# Occulow-Breakout.net
KiCad netlist of a schematic drawn in EAGLE
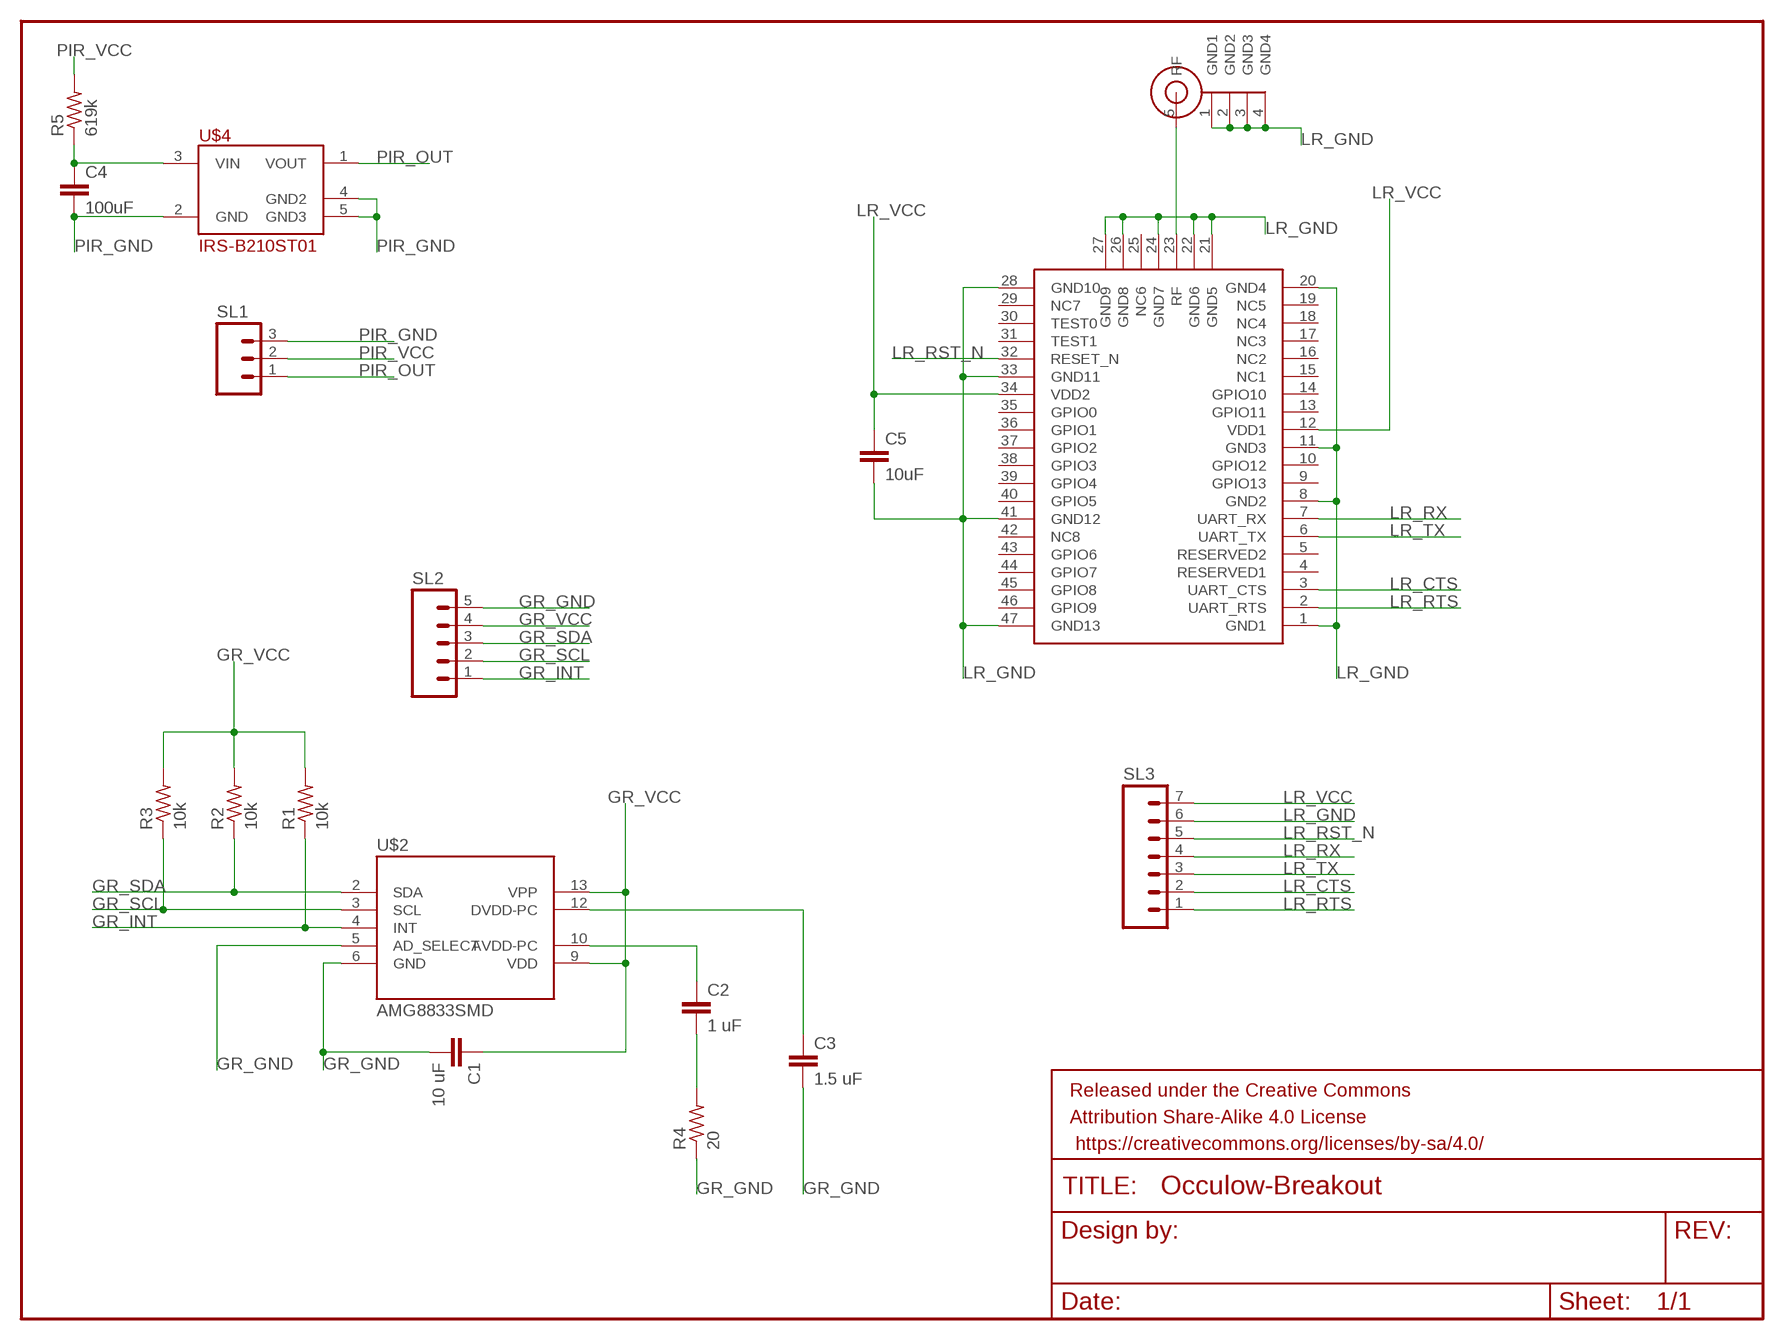
[diagram p0: schematic, sheet 1]

(export (version "E")
  (design (tool "Eeschema 10.0.6"))
  (components
    (comp (ref "C1")
      (value "10 uF")
      (footprint "eagle-import:C1206")
      (libsource (lib "eagle-import") (part "C-EUC1206"))
    )
    (comp (ref "C2")
      (value "1 uF")
      (footprint "eagle-import:C1206")
      (libsource (lib "eagle-import") (part "C-EUC1206"))
    )
    (comp (ref "C3")
      (value "1.5 uF")
      (footprint "eagle-import:C1206")
      (libsource (lib "eagle-import") (part "C-EUC1206"))
    )
    (comp (ref "C4")
      (value "100uF")
      (footprint "eagle-import:C1206")
      (libsource (lib "eagle-import") (part "C-EUC1206"))
    )
    (comp (ref "C5")
      (value "10uF")
      (footprint "eagle-import:C1206")
      (libsource (lib "eagle-import") (part "C-EUC1206"))
    )
    (comp (ref "FRAME1")
      (value "FRAME-LETTER")
      (footprint "eagle-import:CREATIVE_COMMONS")
      (libsource (lib "eagle-import") (part "FRAME-LETTER"))
    )
    (comp (ref "R1")
      (value "10k")
      (footprint "eagle-import:R1206")
      (libsource (lib "eagle-import") (part "R-US_R1206"))
    )
    (comp (ref "R2")
      (value "10k")
      (footprint "eagle-import:R1206")
      (libsource (lib "eagle-import") (part "R-US_R1206"))
    )
    (comp (ref "R3")
      (value "10k")
      (footprint "eagle-import:R1206")
      (libsource (lib "eagle-import") (part "R-US_R1206"))
    )
    (comp (ref "R4")
      (value "20")
      (footprint "eagle-import:R1206")
      (libsource (lib "eagle-import") (part "R-US_R1206"))
    )
    (comp (ref "R5")
      (value "619k")
      (footprint "eagle-import:R1206")
      (libsource (lib "eagle-import") (part "R-US_R1206"))
    )
    (comp (ref "SL1")
      (value "M03")
      (footprint "eagle-import:03P")
      (libsource (lib "eagle-import") (part "M03"))
    )
    (comp (ref "SL2")
      (value "M05")
      (footprint "eagle-import:05P")
      (libsource (lib "eagle-import") (part "M05"))
    )
    (comp (ref "SL3")
      (value "M07")
      (footprint "eagle-import:07P")
      (libsource (lib "eagle-import") (part "M07"))
    )
    (comp (ref "U$1")
      (value "RN2903")
      (footprint "eagle-import:RN2903")
      (libsource (lib "eagle-import") (part "RN2903"))
    )
    (comp (ref "U$2")
      (value "AMG8833SMD")
      (footprint "eagle-import:AMG8833")
      (libsource (lib "eagle-import") (part "AMG8833SMD"))
    )
    (comp (ref "U$3")
      (value "SMA-JACKFEMALE")
      (footprint "eagle-import:SMA-JACK")
      (libsource (lib "eagle-import") (part "SMA-JACKFEMALE"))
    )
    (comp (ref "U$4")
      (value "IRS-B210ST01")
      (footprint "eagle-import:IRS-B210ST01")
      (libsource (lib "eagle-import") (part "IRS-B210ST01"))
    )
  )
  (nets
    (net (code "1") (name "/GR_GND") (class "Default")
      (node (ref "C1") (pin "2") (pinfunction "2_2") (pintype "passive"))
      (node (ref "C3") (pin "2") (pinfunction "2_2") (pintype "passive"))
      (node (ref "R4") (pin "1") (pinfunction "1_1") (pintype "passive"))
      (node (ref "SL2") (pin "5") (pinfunction "5_5") (pintype "passive"))
      (node (ref "U$2") (pin "5") (pinfunction "AD_SELECT_5") (pintype "bidirectional"))
      (node (ref "U$2") (pin "6") (pinfunction "GND_6") (pintype "bidirectional"))
    )
    (net (code "2") (name "/GR_INT") (class "Default")
      (node (ref "R1") (pin "1") (pinfunction "1_1") (pintype "passive"))
      (node (ref "SL2") (pin "1") (pinfunction "1_1") (pintype "passive"))
      (node (ref "U$2") (pin "4") (pinfunction "INT_4") (pintype "bidirectional"))
    )
    (net (code "3") (name "/GR_SCL") (class "Default")
      (node (ref "R3") (pin "1") (pinfunction "1_1") (pintype "passive"))
      (node (ref "SL2") (pin "2") (pinfunction "2_2") (pintype "passive"))
      (node (ref "U$2") (pin "3") (pinfunction "SCL_3") (pintype "bidirectional"))
    )
    (net (code "4") (name "/GR_SDA") (class "Default")
      (node (ref "R2") (pin "1") (pinfunction "1_1") (pintype "passive"))
      (node (ref "SL2") (pin "3") (pinfunction "3_3") (pintype "passive"))
      (node (ref "U$2") (pin "2") (pinfunction "SDA_2") (pintype "bidirectional"))
    )
    (net (code "5") (name "/GR_VCC") (class "Default")
      (node (ref "C1") (pin "1") (pinfunction "1_1") (pintype "passive"))
      (node (ref "R1") (pin "2") (pinfunction "2_2") (pintype "passive"))
      (node (ref "R2") (pin "2") (pinfunction "2_2") (pintype "passive"))
      (node (ref "R3") (pin "2") (pinfunction "2_2") (pintype "passive"))
      (node (ref "SL2") (pin "4") (pinfunction "4_4") (pintype "passive"))
      (node (ref "U$2") (pin "13") (pinfunction "VPP_13") (pintype "bidirectional"))
      (node (ref "U$2") (pin "9") (pinfunction "VDD_9") (pintype "bidirectional"))
    )
    (net (code "6") (name "/LR_CTS") (class "Default")
      (node (ref "SL3") (pin "2") (pinfunction "2_2") (pintype "passive"))
      (node (ref "U$1") (pin "3") (pinfunction "UART_CTS_3") (pintype "bidirectional"))
    )
    (net (code "7") (name "/LR_GND") (class "Default")
      (node (ref "C5") (pin "2") (pinfunction "2_2") (pintype "passive"))
      (node (ref "SL3") (pin "6") (pinfunction "6_6") (pintype "passive"))
      (node (ref "U$1") (pin "1") (pinfunction "GND1_1") (pintype "bidirectional"))
      (node (ref "U$1") (pin "11") (pinfunction "GND3_11") (pintype "bidirectional"))
      (node (ref "U$1") (pin "20") (pinfunction "GND4_20") (pintype "bidirectional"))
      (node (ref "U$1") (pin "21") (pinfunction "GND5_21") (pintype "bidirectional"))
      (node (ref "U$1") (pin "22") (pinfunction "GND6_22") (pintype "bidirectional"))
      (node (ref "U$1") (pin "24") (pinfunction "GND7_24") (pintype "bidirectional"))
      (node (ref "U$1") (pin "26") (pinfunction "GND8_26") (pintype "bidirectional"))
      (node (ref "U$1") (pin "27") (pinfunction "GND9_27") (pintype "bidirectional"))
      (node (ref "U$1") (pin "28") (pinfunction "GND10_28") (pintype "bidirectional"))
      (node (ref "U$1") (pin "33") (pinfunction "GND11_33") (pintype "bidirectional"))
      (node (ref "U$1") (pin "41") (pinfunction "GND12_41") (pintype "bidirectional"))
      (node (ref "U$1") (pin "47") (pinfunction "GND13_47") (pintype "bidirectional"))
      (node (ref "U$1") (pin "8") (pinfunction "GND2_8") (pintype "bidirectional"))
      (node (ref "U$3") (pin "1") (pinfunction "GND1_1") (pintype "bidirectional"))
      (node (ref "U$3") (pin "2") (pinfunction "GND2_2") (pintype "bidirectional"))
      (node (ref "U$3") (pin "3") (pinfunction "GND3_3") (pintype "bidirectional"))
      (node (ref "U$3") (pin "4") (pinfunction "GND4_4") (pintype "bidirectional"))
    )
    (net (code "8") (name "/LR_RST_N") (class "Default")
      (node (ref "SL3") (pin "5") (pinfunction "5_5") (pintype "passive"))
      (node (ref "U$1") (pin "32") (pinfunction "RESET_N_32") (pintype "bidirectional"))
    )
    (net (code "9") (name "/LR_RTS") (class "Default")
      (node (ref "SL3") (pin "1") (pinfunction "1_1") (pintype "passive"))
      (node (ref "U$1") (pin "2") (pinfunction "UART_RTS_2") (pintype "bidirectional"))
    )
    (net (code "10") (name "/LR_RX") (class "Default")
      (node (ref "SL3") (pin "4") (pinfunction "4_4") (pintype "passive"))
      (node (ref "U$1") (pin "7") (pinfunction "UART_RX_7") (pintype "bidirectional"))
    )
    (net (code "11") (name "/LR_TX") (class "Default")
      (node (ref "SL3") (pin "3") (pinfunction "3_3") (pintype "passive"))
      (node (ref "U$1") (pin "6") (pinfunction "UART_TX_6") (pintype "bidirectional"))
    )
    (net (code "12") (name "/LR_VCC") (class "Default")
      (node (ref "C5") (pin "1") (pinfunction "1_1") (pintype "passive"))
      (node (ref "SL3") (pin "7") (pinfunction "7_7") (pintype "passive"))
      (node (ref "U$1") (pin "12") (pinfunction "VDD1_12") (pintype "bidirectional"))
      (node (ref "U$1") (pin "34") (pinfunction "VDD2_34") (pintype "bidirectional"))
    )
    (net (code "13") (name "/PIR_GND") (class "Default")
      (node (ref "C4") (pin "2") (pinfunction "2_2") (pintype "passive"))
      (node (ref "SL1") (pin "3") (pinfunction "3_3") (pintype "passive"))
      (node (ref "U$4") (pin "2") (pinfunction "GND_2") (pintype "bidirectional"))
      (node (ref "U$4") (pin "4") (pinfunction "GND2_4") (pintype "bidirectional"))
      (node (ref "U$4") (pin "5") (pinfunction "GND3_5") (pintype "bidirectional"))
    )
    (net (code "14") (name "/PIR_OUT") (class "Default")
      (node (ref "SL1") (pin "1") (pinfunction "1_1") (pintype "passive"))
      (node (ref "U$4") (pin "1") (pinfunction "VOUT_1") (pintype "bidirectional"))
    )
    (net (code "15") (name "/PIR_VCC") (class "Default")
      (node (ref "R5") (pin "2") (pinfunction "2_2") (pintype "passive"))
      (node (ref "SL1") (pin "2") (pinfunction "2_2") (pintype "passive"))
    )
    (net (code "16") (name "Net-(C2-Pad2)") (class "Default")
      (node (ref "C2") (pin "2") (pinfunction "2_2") (pintype "passive"))
      (node (ref "R4") (pin "2") (pinfunction "2_2") (pintype "passive"))
    )
    (net (code "17") (name "Net-(U$1-RF)") (class "Default")
      (node (ref "U$1") (pin "23") (pinfunction "RF_23") (pintype "bidirectional"))
      (node (ref "U$3") (pin "5") (pinfunction "RF_5") (pintype "bidirectional"))
    )
    (net (code "18") (name "Net-(U$2-AVDD-PC)") (class "Default")
      (node (ref "C2") (pin "1") (pinfunction "1_1") (pintype "passive"))
      (node (ref "U$2") (pin "10") (pinfunction "AVDD-PC_10") (pintype "bidirectional"))
    )
    (net (code "19") (name "Net-(U$2-DVDD-PC)") (class "Default")
      (node (ref "C3") (pin "1") (pinfunction "1_1") (pintype "passive"))
      (node (ref "U$2") (pin "12") (pinfunction "DVDD-PC_12") (pintype "bidirectional"))
    )
    (net (code "20") (name "Net-(U$4-VIN)") (class "Default")
      (node (ref "C4") (pin "1") (pinfunction "1_1") (pintype "passive"))
      (node (ref "R5") (pin "1") (pinfunction "1_1") (pintype "passive"))
      (node (ref "U$4") (pin "3") (pinfunction "VIN_3") (pintype "bidirectional"))
    )
    (net (code "21") (name "unconnected-(U$1-GPIO0-Pad35)") (class "Default")
      (node (ref "U$1") (pin "35") (pinfunction "GPIO0_35") (pintype "bidirectional"))
    )
    (net (code "22") (name "unconnected-(U$1-GPIO1-Pad36)") (class "Default")
      (node (ref "U$1") (pin "36") (pinfunction "GPIO1_36") (pintype "bidirectional"))
    )
    (net (code "23") (name "unconnected-(U$1-GPIO2-Pad37)") (class "Default")
      (node (ref "U$1") (pin "37") (pinfunction "GPIO2_37") (pintype "bidirectional"))
    )
    (net (code "24") (name "unconnected-(U$1-GPIO3-Pad38)") (class "Default")
      (node (ref "U$1") (pin "38") (pinfunction "GPIO3_38") (pintype "bidirectional"))
    )
    (net (code "25") (name "unconnected-(U$1-GPIO4-Pad39)") (class "Default")
      (node (ref "U$1") (pin "39") (pinfunction "GPIO4_39") (pintype "bidirectional"))
    )
    (net (code "26") (name "unconnected-(U$1-GPIO5-Pad40)") (class "Default")
      (node (ref "U$1") (pin "40") (pinfunction "GPIO5_40") (pintype "bidirectional"))
    )
    (net (code "27") (name "unconnected-(U$1-GPIO6-Pad43)") (class "Default")
      (node (ref "U$1") (pin "43") (pinfunction "GPIO6_43") (pintype "bidirectional"))
    )
    (net (code "28") (name "unconnected-(U$1-GPIO7-Pad44)") (class "Default")
      (node (ref "U$1") (pin "44") (pinfunction "GPIO7_44") (pintype "bidirectional"))
    )
    (net (code "29") (name "unconnected-(U$1-GPIO8-Pad45)") (class "Default")
      (node (ref "U$1") (pin "45") (pinfunction "GPIO8_45") (pintype "bidirectional"))
    )
    (net (code "30") (name "unconnected-(U$1-GPIO9-Pad46)") (class "Default")
      (node (ref "U$1") (pin "46") (pinfunction "GPIO9_46") (pintype "bidirectional"))
    )
    (net (code "31") (name "unconnected-(U$1-GPIO10-Pad14)") (class "Default")
      (node (ref "U$1") (pin "14") (pinfunction "GPIO10_14") (pintype "bidirectional"))
    )
    (net (code "32") (name "unconnected-(U$1-GPIO11-Pad13)") (class "Default")
      (node (ref "U$1") (pin "13") (pinfunction "GPIO11_13") (pintype "bidirectional"))
    )
    (net (code "33") (name "unconnected-(U$1-GPIO12-Pad10)") (class "Default")
      (node (ref "U$1") (pin "10") (pinfunction "GPIO12_10") (pintype "bidirectional"))
    )
    (net (code "34") (name "unconnected-(U$1-GPIO13-Pad9)") (class "Default")
      (node (ref "U$1") (pin "9") (pinfunction "GPIO13_9") (pintype "bidirectional"))
    )
    (net (code "35") (name "unconnected-(U$1-NC1-Pad15)") (class "Default")
      (node (ref "U$1") (pin "15") (pinfunction "NC1_15") (pintype "bidirectional"))
    )
    (net (code "36") (name "unconnected-(U$1-NC2-Pad16)") (class "Default")
      (node (ref "U$1") (pin "16") (pinfunction "NC2_16") (pintype "bidirectional"))
    )
    (net (code "37") (name "unconnected-(U$1-NC3-Pad17)") (class "Default")
      (node (ref "U$1") (pin "17") (pinfunction "NC3_17") (pintype "bidirectional"))
    )
    (net (code "38") (name "unconnected-(U$1-NC4-Pad18)") (class "Default")
      (node (ref "U$1") (pin "18") (pinfunction "NC4_18") (pintype "bidirectional"))
    )
    (net (code "39") (name "unconnected-(U$1-NC5-Pad19)") (class "Default")
      (node (ref "U$1") (pin "19") (pinfunction "NC5_19") (pintype "bidirectional"))
    )
    (net (code "40") (name "unconnected-(U$1-NC6-Pad25)") (class "Default")
      (node (ref "U$1") (pin "25") (pinfunction "NC6_25") (pintype "bidirectional"))
    )
    (net (code "41") (name "unconnected-(U$1-NC7-Pad29)") (class "Default")
      (node (ref "U$1") (pin "29") (pinfunction "NC7_29") (pintype "bidirectional"))
    )
    (net (code "42") (name "unconnected-(U$1-NC8-Pad42)") (class "Default")
      (node (ref "U$1") (pin "42") (pinfunction "NC8_42") (pintype "bidirectional"))
    )
    (net (code "43") (name "unconnected-(U$1-RESERVED1-Pad4)") (class "Default")
      (node (ref "U$1") (pin "4") (pinfunction "RESERVED1_4") (pintype "bidirectional"))
    )
    (net (code "44") (name "unconnected-(U$1-RESERVED2-Pad5)") (class "Default")
      (node (ref "U$1") (pin "5") (pinfunction "RESERVED2_5") (pintype "bidirectional"))
    )
    (net (code "45") (name "unconnected-(U$1-TEST0-Pad30)") (class "Default")
      (node (ref "U$1") (pin "30") (pinfunction "TEST0_30") (pintype "bidirectional"))
    )
    (net (code "46") (name "unconnected-(U$1-TEST1-Pad31)") (class "Default")
      (node (ref "U$1") (pin "31") (pinfunction "TEST1_31") (pintype "bidirectional"))
    )
  )
)
